# 4_IMU.net
KiCad netlist of a schematic drawn in Altium Designer
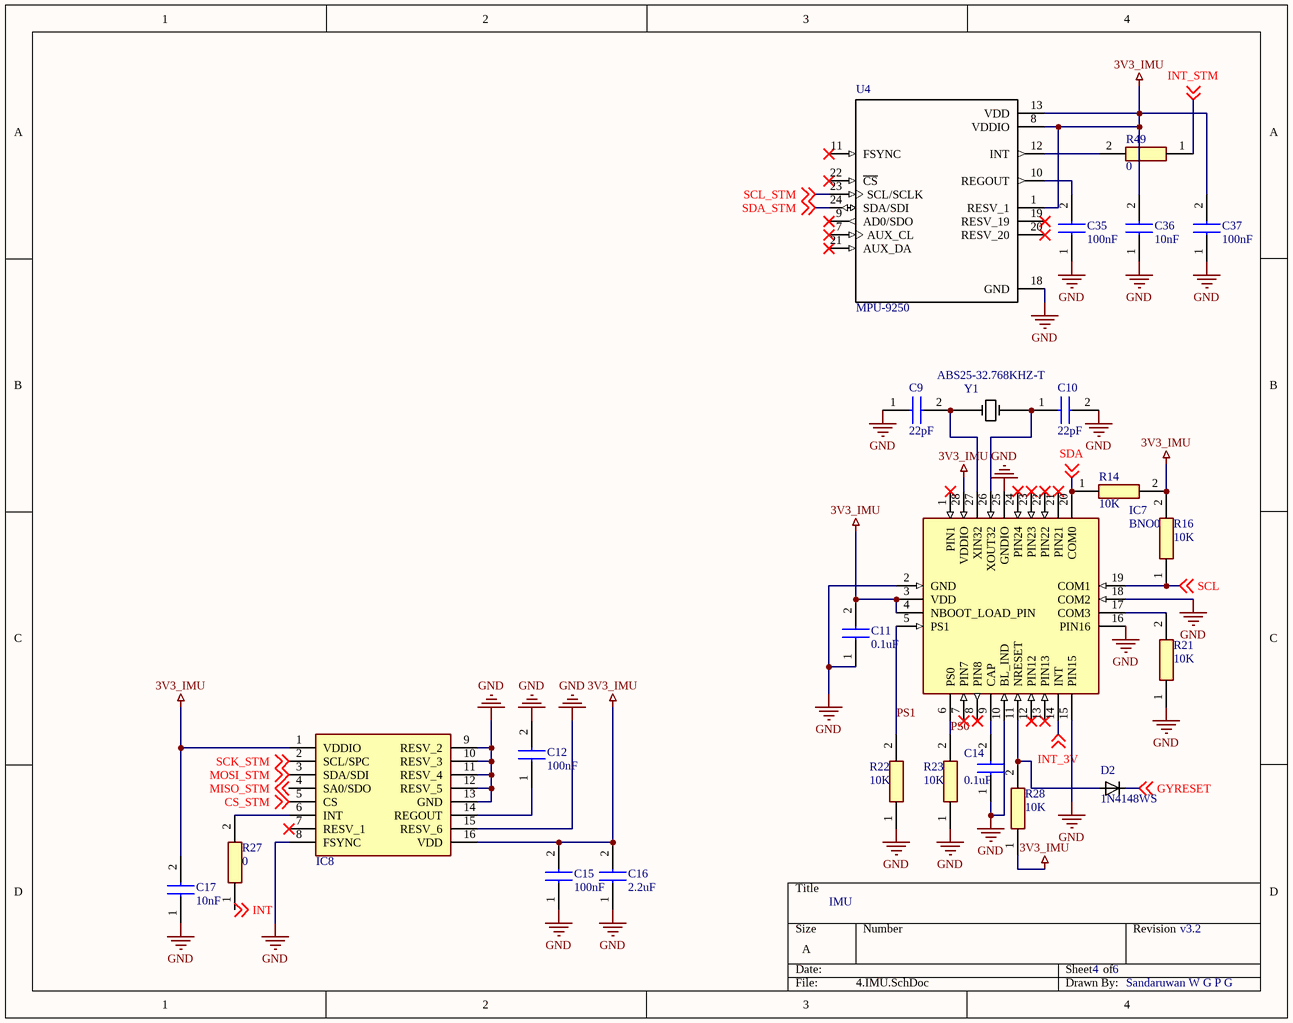
[diagram p0: 4.IMU.SchDoc]

(export (version "E")
  (design (tool "Eeschema 10.0.6"))
  (components
    (comp (ref "C9")
      (value "22pF")
      (footprint "*CAPC1608X95N")
      (description "Capacitor")
      (fields (field (name "Comment") "capacitor 0603"))
      (libsource (lib "micromouse library") (part "capacitor 0603"))
    )
    (comp (ref "C10")
      (value "22pF")
      (footprint "*CAPC1608X95N")
      (description "Capacitor")
      (fields (field (name "Comment") "capacitor 0603"))
      (libsource (lib "micromouse library") (part "capacitor 0603"))
    )
    (comp (ref "C11")
      (value "0.1uF")
      (footprint "*CAPC1608X95N")
      (description "Capacitor")
      (fields (field (name "Comment") "capacitor 0603"))
      (libsource (lib "micromouse library") (part "capacitor 0603"))
    )
    (comp (ref "C12")
      (value "100nF")
      (footprint "*CAPC1608X95N")
      (description "Capacitor")
      (fields (field (name "Comment") "capacitor 0603"))
      (libsource (lib "micromouse library") (part "capacitor 0603"))
    )
    (comp (ref "C14")
      (value "0.1uF")
      (footprint "*CAPC1608X95N")
      (description "Capacitor")
      (fields (field (name "Comment") "capacitor 0603"))
      (libsource (lib "micromouse library") (part "capacitor 0603"))
    )
    (comp (ref "C15")
      (value "100nF")
      (footprint "*CAPC1608X95N")
      (description "Capacitor")
      (fields (field (name "Comment") "capacitor 0603"))
      (libsource (lib "micromouse library") (part "capacitor 0603"))
    )
    (comp (ref "C16")
      (value "2.2uF")
      (footprint "*CAPC1608X95N")
      (description "Capacitor")
      (fields (field (name "Comment") "capacitor 0603"))
      (libsource (lib "micromouse library") (part "capacitor 0603"))
    )
    (comp (ref "C17")
      (value "10nF")
      (footprint "*CAPC1608X95N")
      (description "Capacitor")
      (fields (field (name "Comment") "capacitor 0603"))
      (libsource (lib "micromouse library") (part "capacitor 0603"))
    )
    (comp (ref "C35")
      (value "100nF")
      (footprint "*CAPC1608X95N")
      (description "Capacitor")
      (fields (field (name "Comment") "capacitor 0603"))
      (libsource (lib "micromouse library") (part "capacitor 0603"))
    )
    (comp (ref "C36")
      (value "10nF")
      (footprint "*CAPC1608X95N")
      (description "Capacitor")
      (fields (field (name "Comment") "capacitor 0603"))
      (libsource (lib "micromouse library") (part "capacitor 0603"))
    )
    (comp (ref "C37")
      (value "100nF")
      (footprint "*CAPC1608X95N")
      (description "Capacitor")
      (fields (field (name "Comment") "capacitor 0603"))
      (libsource (lib "micromouse library") (part "capacitor 0603"))
    )
    (comp (ref "D2")
      (value "1N4148WS")
      (footprint "*SOD323_1N4148WS(Primary)")
      (description "Diode Switching 75V 0.3A 2-Pin SOD-323 T/R")
      (fields (field (name "MF") "ON Semiconductor"))
      (libsource (lib "micromouse library") (part "1N4148WS"))
    )
    (comp (ref "IC7")
      (value "BNO055")
      (footprint "micromouse pcb library:BNO055")
      (description "Integrated Circuit")
      (fields (field (name "MOUSER PART NUMBER") "262-BNO055"))
      (libsource (lib "*") (part "BNO055"))
    )
    (comp (ref "IC8")
      (value "ICM20602")
      (footprint "PULL-BACK-QFN-16")
      (description "Integrated Circuit")
      (libsource (lib "micromouse library") (part "ICM20602"))
    )
    (comp (ref "R14")
      (value "10K")
      (footprint "RESC1608X55N")
      (description "Resistor")
      (fields (field (name "Comment") "resistor"))
      (libsource (lib "") (part "resistor_1"))
    )
    (comp (ref "R16")
      (value "10K")
      (footprint "RESC1608X55N")
      (description "Resistor")
      (fields (field (name "Comment") "resistor"))
      (libsource (lib "micromouse library") (part "resistor"))
    )
    (comp (ref "R21")
      (value "10K")
      (footprint "RESC1608X55N")
      (description "Resistor")
      (fields (field (name "Comment") "resistor"))
      (libsource (lib "micromouse library") (part "resistor"))
    )
    (comp (ref "R22")
      (value "10K")
      (footprint "RESC1608X55N")
      (description "Resistor")
      (fields (field (name "Comment") "resistor"))
      (libsource (lib "micromouse library") (part "resistor"))
    )
    (comp (ref "R23")
      (value "10K")
      (footprint "RESC1608X55N")
      (description "Resistor")
      (fields (field (name "Comment") "resistor"))
      (libsource (lib "micromouse library") (part "resistor"))
    )
    (comp (ref "R27")
      (value "0")
      (footprint "RESC1608X55N")
      (description "Resistor")
      (fields (field (name "Comment") "resistor"))
      (libsource (lib "micromouse library") (part "resistor"))
    )
    (comp (ref "R28")
      (value "10K")
      (footprint "RESC1608X55N")
      (description "Resistor")
      (fields (field (name "Comment") "resistor"))
      (libsource (lib "micromouse library") (part "resistor"))
    )
    (comp (ref "R49")
      (value "0")
      (footprint "RESC1608X55N")
      (description "Resistor")
      (fields (field (name "Comment") "resistor"))
      (libsource (lib "") (part "resistor_2"))
    )
    (comp (ref "U4")
      (value "MPU-9250")
      (footprint "*QFN40P300X300X105-24N")
      (description "IMUs - Inertial Measurement Units RECOMMENDED ALT 410-ICM-20948")
      (fields (field (name "MF") "TDK InvenSense"))
      (libsource (lib "micromouse library") (part "MPU-9250"))
    )
    (comp (ref "Y1")
      (value "ABS25-32.768KHZ-T")
      (footprint "*XTAL_ABS25-32.768KHZ-6-1-T")
      (description "32.768 Mhz Plastic Smt Low Pro")
      (fields (field (name "MP") "ABS25-32.768KHZ") (field (name "MF") "Abracon LLC"))
      (libsource (lib "micromouse library") (part "ABS25-32.768KHZ-T"))
    )
  )
  (nets
    (net (code "1") (name "/PS0") (class "Default")
      (node (ref "IC7") (pin "6") (pinfunction "PS0_6") (pintype "power_in"))
      (node (ref "R23") (pin "2") (pinfunction "2_2") (pintype "passive"))
    )
    (net (code "2") (name "/PS1") (class "Default")
      (node (ref "IC7") (pin "5") (pinfunction "PS1_5") (pintype "input"))
      (node (ref "R22") (pin "2") (pinfunction "2_2") (pintype "passive"))
    )
    (net (code "3") (name "3V3_IMU") (class "Default")
      (node (ref "C11") (pin "2") (pinfunction "2_2") (pintype "passive"))
      (node (ref "C15") (pin "2") (pinfunction "2_2") (pintype "passive"))
      (node (ref "C16") (pin "2") (pinfunction "2_2") (pintype "passive"))
      (node (ref "C17") (pin "2") (pinfunction "2_2") (pintype "passive"))
      (node (ref "C36") (pin "2") (pinfunction "2_2") (pintype "passive"))
      (node (ref "C37") (pin "2") (pinfunction "2_2") (pintype "passive"))
      (node (ref "IC7") (pin "28") (pinfunction "VDDIO_28") (pintype "input"))
      (node (ref "IC7") (pin "3") (pinfunction "VDD_3") (pintype "power_in"))
      (node (ref "IC7") (pin "4") (pinfunction "NBOOT_LOAD_PIN_4") (pintype "power_in"))
      (node (ref "IC8") (pin "1") (pinfunction "VDDIO_1") (pintype "passive"))
      (node (ref "IC8") (pin "16") (pinfunction "VDD_16") (pintype "passive"))
      (node (ref "R14") (pin "2") (pinfunction "2_2") (pintype "passive"))
      (node (ref "R16") (pin "2") (pinfunction "2_2") (pintype "passive"))
      (node (ref "R28") (pin "1") (pinfunction "1_1") (pintype "passive"))
      (node (ref "U4") (pin "1") (pinfunction "RESV_1_1") (pintype "passive"))
      (node (ref "U4") (pin "13") (pinfunction "VDD_13") (pintype "power_in"))
      (node (ref "U4") (pin "8") (pinfunction "VDDIO_8") (pintype "power_in"))
    )
    (net (code "4") (name "CS_STM") (class "Default")
      (node (ref "IC8") (pin "5") (pinfunction "CS_5") (pintype "passive"))
    )
    (net (code "5") (name "GND") (class "Default")
      (node (ref "C10") (pin "2") (pinfunction "2_2") (pintype "passive"))
      (node (ref "C11") (pin "1") (pinfunction "1_1") (pintype "passive"))
      (node (ref "C12") (pin "2") (pinfunction "2_2") (pintype "passive"))
      (node (ref "C14") (pin "1") (pinfunction "1_1") (pintype "passive"))
      (node (ref "C15") (pin "1") (pinfunction "1_1") (pintype "passive"))
      (node (ref "C16") (pin "1") (pinfunction "1_1") (pintype "passive"))
      (node (ref "C17") (pin "1") (pinfunction "1_1") (pintype "passive"))
      (node (ref "C35") (pin "1") (pinfunction "1_1") (pintype "passive"))
      (node (ref "C36") (pin "1") (pinfunction "1_1") (pintype "passive"))
      (node (ref "C37") (pin "1") (pinfunction "1_1") (pintype "passive"))
      (node (ref "C9") (pin "1") (pinfunction "1_1") (pintype "passive"))
      (node (ref "IC7") (pin "10") (pinfunction "BL_IND_10") (pintype "input"))
      (node (ref "IC7") (pin "15") (pinfunction "PIN15_15") (pintype "passive"))
      (node (ref "IC7") (pin "16") (pinfunction "PIN16_16") (pintype "passive"))
      (node (ref "IC7") (pin "18") (pinfunction "COM2_18") (pintype "input"))
      (node (ref "IC7") (pin "2") (pinfunction "GND_2") (pintype "input"))
      (node (ref "IC7") (pin "25") (pinfunction "GNDIO_25") (pintype "passive"))
      (node (ref "IC8") (pin "10") (pinfunction "RESV_3_10") (pintype "passive"))
      (node (ref "IC8") (pin "11") (pinfunction "RESV_4_11") (pintype "passive"))
      (node (ref "IC8") (pin "12") (pinfunction "RESV_5_12") (pintype "passive"))
      (node (ref "IC8") (pin "13") (pinfunction "GND_13") (pintype "passive"))
      (node (ref "IC8") (pin "15") (pinfunction "RESV_6_15") (pintype "passive"))
      (node (ref "IC8") (pin "8") (pinfunction "FSYNC_8") (pintype "passive"))
      (node (ref "IC8") (pin "9") (pinfunction "RESV_2_9") (pintype "passive"))
      (node (ref "R21") (pin "1") (pinfunction "1_1") (pintype "passive"))
      (node (ref "R22") (pin "1") (pinfunction "1_1") (pintype "passive"))
      (node (ref "R23") (pin "1") (pinfunction "1_1") (pintype "passive"))
      (node (ref "U4") (pin "18") (pinfunction "GND_18") (pintype "power_in"))
    )
    (net (code "6") (name "GYRESET") (class "Default")
      (node (ref "D2") (pin "C") (pinfunction "C_C") (pintype "passive"))
    )
    (net (code "7") (name "INT") (class "Default")
      (node (ref "R27") (pin "1") (pinfunction "1_1") (pintype "passive"))
    )
    (net (code "8") (name "INT_3V") (class "Default")
      (node (ref "IC7") (pin "14") (pinfunction "INT_14") (pintype "passive"))
    )
    (net (code "9") (name "INT_STM") (class "Default")
      (node (ref "R49") (pin "1") (pinfunction "1_1") (pintype "passive"))
    )
    (net (code "10") (name "MISO_STM") (class "Default")
      (node (ref "IC8") (pin "4") (pinfunction "SA0/SDO_4") (pintype "passive"))
    )
    (net (code "11") (name "MOSI_STM") (class "Default")
      (node (ref "IC8") (pin "3") (pinfunction "SDA/SDI_3") (pintype "passive"))
    )
    (net (code "12") (name "Net-(IC7-CAP)") (class "Default")
      (node (ref "C14") (pin "2") (pinfunction "2_2") (pintype "passive"))
      (node (ref "IC7") (pin "9") (pinfunction "CAP_9") (pintype "power_in"))
    )
    (net (code "13") (name "Net-(IC7-COM3)") (class "Default")
      (node (ref "IC7") (pin "17") (pinfunction "COM3_17") (pintype "passive"))
      (node (ref "R21") (pin "2") (pinfunction "2_2") (pintype "passive"))
    )
    (net (code "14") (name "Net-(IC7-NRESET)") (class "Default")
      (node (ref "D2") (pin "A") (pinfunction "A_A") (pintype "passive"))
      (node (ref "IC7") (pin "11") (pinfunction "NRESET_11") (pintype "input"))
      (node (ref "R28") (pin "2") (pinfunction "2_2") (pintype "passive"))
    )
    (net (code "15") (name "Net-(IC7-XIN32)") (class "Default")
      (node (ref "C9") (pin "2") (pinfunction "2_2") (pintype "passive"))
      (node (ref "IC7") (pin "27") (pinfunction "XIN32_27") (pintype "passive"))
      (node (ref "Y1") (pin "4") (pinfunction "4_4") (pintype "passive"))
    )
    (net (code "16") (name "Net-(IC7-XOUT32)") (class "Default")
      (node (ref "C10") (pin "1") (pinfunction "1_1") (pintype "passive"))
      (node (ref "IC7") (pin "26") (pinfunction "XOUT32_26") (pintype "input"))
      (node (ref "Y1") (pin "1") (pinfunction "1_1") (pintype "passive"))
    )
    (net (code "17") (name "Net-(IC8-INT)") (class "Default")
      (node (ref "IC8") (pin "6") (pinfunction "INT_6") (pintype "passive"))
      (node (ref "R27") (pin "2") (pinfunction "2_2") (pintype "passive"))
    )
    (net (code "18") (name "Net-(IC8-REGOUT)") (class "Default")
      (node (ref "C12") (pin "1") (pinfunction "1_1") (pintype "passive"))
      (node (ref "IC8") (pin "14") (pinfunction "REGOUT_14") (pintype "passive"))
    )
    (net (code "19") (name "Net-(U4-INT)") (class "Default")
      (node (ref "R49") (pin "2") (pinfunction "2_2") (pintype "passive"))
      (node (ref "U4") (pin "12") (pinfunction "INT_12") (pintype "output"))
    )
    (net (code "20") (name "Net-(U4-REGOUT)") (class "Default")
      (node (ref "C35") (pin "2") (pinfunction "2_2") (pintype "passive"))
      (node (ref "U4") (pin "10") (pinfunction "REGOUT_10") (pintype "output"))
    )
    (net (code "21") (name "SCK_STM") (class "Default")
      (node (ref "IC8") (pin "2") (pinfunction "SCL/SPC_2") (pintype "passive"))
    )
    (net (code "22") (name "SCL") (class "Default")
      (node (ref "IC7") (pin "19") (pinfunction "COM1_19") (pintype "input"))
      (node (ref "R16") (pin "1") (pinfunction "1_1") (pintype "passive"))
    )
    (net (code "23") (name "SCL_STM") (class "Default")
      (node (ref "U4") (pin "23") (pinfunction "SCL/SCLK_23") (pintype "input"))
    )
    (net (code "24") (name "SDA") (class "Default")
      (node (ref "IC7") (pin "20") (pinfunction "COM0_20") (pintype "passive"))
      (node (ref "R14") (pin "1") (pinfunction "1_1") (pintype "passive"))
    )
    (net (code "25") (name "SDA_STM") (class "Default")
      (node (ref "U4") (pin "24") (pinfunction "SDA/SDI_24") (pintype "bidirectional"))
    )
    (net (code "26") (name "unconnected-(IC7-PIN1-Pad1)") (class "Default")
      (node (ref "IC7") (pin "1") (pinfunction "PIN1_1") (pintype "input+no_connect"))
    )
    (net (code "27") (name "unconnected-(IC7-PIN7-Pad7)") (class "Default")
      (node (ref "IC7") (pin "7") (pinfunction "PIN7_7") (pintype "input+no_connect"))
    )
    (net (code "28") (name "unconnected-(IC7-PIN8-Pad8)") (class "Default")
      (node (ref "IC7") (pin "8") (pinfunction "PIN8_8") (pintype "output+no_connect"))
    )
    (net (code "29") (name "unconnected-(IC7-PIN12-Pad12)") (class "Default")
      (node (ref "IC7") (pin "12") (pinfunction "PIN12_12") (pintype "input+no_connect"))
    )
    (net (code "30") (name "unconnected-(IC7-PIN13-Pad13)") (class "Default")
      (node (ref "IC7") (pin "13") (pinfunction "PIN13_13") (pintype "input+no_connect"))
    )
    (net (code "31") (name "unconnected-(IC7-PIN21-Pad21)") (class "Default")
      (node (ref "IC7") (pin "21") (pinfunction "PIN21_21") (pintype "passive+no_connect"))
    )
    (net (code "32") (name "unconnected-(IC7-PIN22-Pad22)") (class "Default")
      (node (ref "IC7") (pin "22") (pinfunction "PIN22_22") (pintype "input+no_connect"))
    )
    (net (code "33") (name "unconnected-(IC7-PIN23-Pad23)") (class "Default")
      (node (ref "IC7") (pin "23") (pinfunction "PIN23_23") (pintype "input+no_connect"))
    )
    (net (code "34") (name "unconnected-(IC7-PIN24-Pad24)") (class "Default")
      (node (ref "IC7") (pin "24") (pinfunction "PIN24_24") (pintype "input+no_connect"))
    )
    (net (code "35") (name "unconnected-(IC8-RESV_1-Pad7)") (class "Default")
      (node (ref "IC8") (pin "7") (pinfunction "RESV_1_7") (pintype "passive+no_connect"))
    )
    (net (code "36") (name "unconnected-(U4-AD0{slash}SDO-Pad9)") (class "Default")
      (node (ref "U4") (pin "9") (pinfunction "AD0/SDO_9") (pintype "output+no_connect"))
    )
    (net (code "37") (name "unconnected-(U4-AUX_CL-Pad7)") (class "Default")
      (node (ref "U4") (pin "7") (pinfunction "AUX_CL_7") (pintype "input+no_connect"))
    )
    (net (code "38") (name "unconnected-(U4-AUX_DA-Pad21)") (class "Default")
      (node (ref "U4") (pin "21") (pinfunction "AUX_DA_21") (pintype "input+no_connect"))
    )
    (net (code "39") (name "unconnected-(U4-FSYNC-Pad11)") (class "Default")
      (node (ref "U4") (pin "11") (pinfunction "FSYNC_11") (pintype "input+no_connect"))
    )
    (net (code "40") (name "unconnected-(U4-RESV_19-Pad19)") (class "Default")
      (node (ref "U4") (pin "19") (pinfunction "RESV_19_19") (pintype "passive+no_connect"))
    )
    (net (code "41") (name "unconnected-(U4-RESV_20-Pad20)") (class "Default")
      (node (ref "U4") (pin "20") (pinfunction "RESV_20_20") (pintype "passive+no_connect"))
    )
    (net (code "42") (name "unconnected-(U4-~{CS}-Pad22)") (class "Default")
      (node (ref "U4") (pin "22") (pinfunction "~{CS}_22") (pintype "input+no_connect"))
    )
  )
)
